# USB-C.net
KiCad netlist of a schematic drawn in Altium Designer
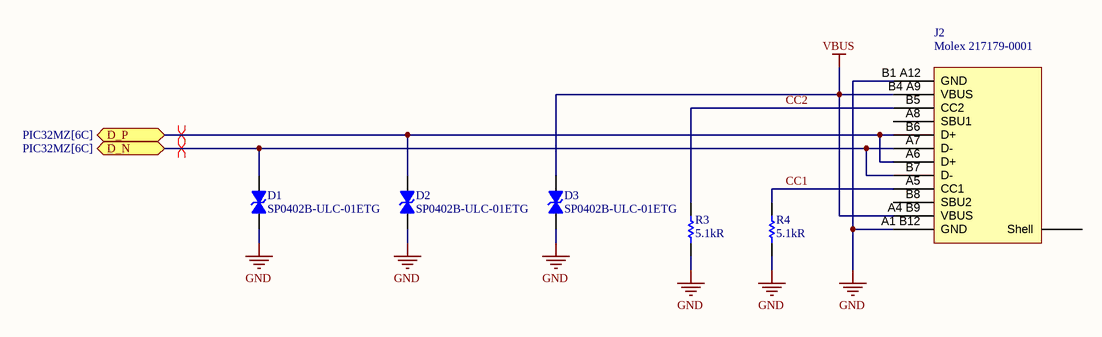
[diagram p0: USB-C.SchDoc]

(export (version "E")
  (design (tool "Eeschema 10.0.6"))
  (components
    (comp (ref "D1")
      (value "SP0402B-ULC-01ETG")
      (footprint "Diode TVS 0402")
      (libsource (lib "x-io") (part "Diode TVS"))
    )
    (comp (ref "D2")
      (value "SP0402B-ULC-01ETG")
      (footprint "Diode TVS 0402")
      (libsource (lib "x-io") (part "Diode TVS"))
    )
    (comp (ref "D3")
      (value "SP0402B-ULC-01ETG")
      (footprint "Diode TVS 0402")
      (libsource (lib "x-io") (part "Diode TVS"))
    )
    (comp (ref "J2")
      (value "Molex 217179-0001")
      (footprint "Molex 217179-0001")
      (libsource (lib "x-io") (part "USB-C Receptacle (16 Pin)"))
    )
    (comp (ref "R3") (value "5.1kR") (footprint "Resistor 0402") (libsource (lib "x-io") (part "Resistor")))
    (comp (ref "R4") (value "5.1kR") (footprint "Resistor 0402") (libsource (lib "x-io") (part "Resistor")))
  )
  (nets
    (net (code "1") (name "/CC1") (class "Default")
      (node (ref "J2") (pin "A5") (pinfunction "CC1_A5") (pintype "passive"))
      (node (ref "R4") (pin "2") (pinfunction "2_2") (pintype "passive"))
    )
    (net (code "2") (name "/CC2") (class "Default")
      (node (ref "J2") (pin "B5") (pinfunction "CC2_B5") (pintype "passive"))
      (node (ref "R3") (pin "2") (pinfunction "2_2") (pintype "passive"))
    )
    (net (code "3") (name "/D_N") (class "Default")
      (node (ref "D1") (pin "1") (pinfunction "*_1") (pintype "passive"))
      (node (ref "J2") (pin "A7") (pinfunction "D-_A7") (pintype "passive"))
      (node (ref "J2") (pin "B7") (pinfunction "D-_B7") (pintype "passive"))
    )
    (net (code "4") (name "/D_P") (class "Default")
      (node (ref "D2") (pin "1") (pinfunction "*_1") (pintype "passive"))
      (node (ref "J2") (pin "A6") (pinfunction "D+_A6") (pintype "passive"))
      (node (ref "J2") (pin "B6") (pinfunction "D+_B6") (pintype "passive"))
    )
    (net (code "5") (name "GND") (class "Default")
      (node (ref "D1") (pin "2") (pinfunction "*_2") (pintype "passive"))
      (node (ref "D2") (pin "2") (pinfunction "*_2") (pintype "passive"))
      (node (ref "D3") (pin "2") (pinfunction "*_2") (pintype "passive"))
      (node (ref "J2") (pin "A1_B12") (pinfunction "GND_A1_B12") (pintype "passive"))
      (node (ref "J2") (pin "B1_A12") (pinfunction "GND_B1_A12") (pintype "passive"))
      (node (ref "R3") (pin "1") (pinfunction "1_1") (pintype "passive"))
      (node (ref "R4") (pin "1") (pinfunction "1_1") (pintype "passive"))
    )
    (net (code "6") (name "VBUS") (class "Default")
      (node (ref "D3") (pin "1") (pinfunction "*_1") (pintype "passive"))
      (node (ref "J2") (pin "A4_B9") (pinfunction "VBUS_A4_B9") (pintype "passive"))
      (node (ref "J2") (pin "B4_A9") (pinfunction "VBUS_B4_A9") (pintype "passive"))
    )
    (net (code "7") (name "unconnected-(J2-PadShell)") (class "Default")
      (node (ref "J2") (pin "Shell") (pinfunction "Shell_Shell") (pintype "passive"))
    )
    (net (code "8") (name "unconnected-(J2-SBU1-PadA8)") (class "Default")
      (node (ref "J2") (pin "A8") (pinfunction "SBU1_A8") (pintype "passive"))
    )
    (net (code "9") (name "unconnected-(J2-SBU2-PadB8)") (class "Default")
      (node (ref "J2") (pin "B8") (pinfunction "SBU2_B8") (pintype "passive"))
    )
  )
)
